# LiPo_Battery_Meter.net
KiCad netlist of a schematic drawn in EAGLE
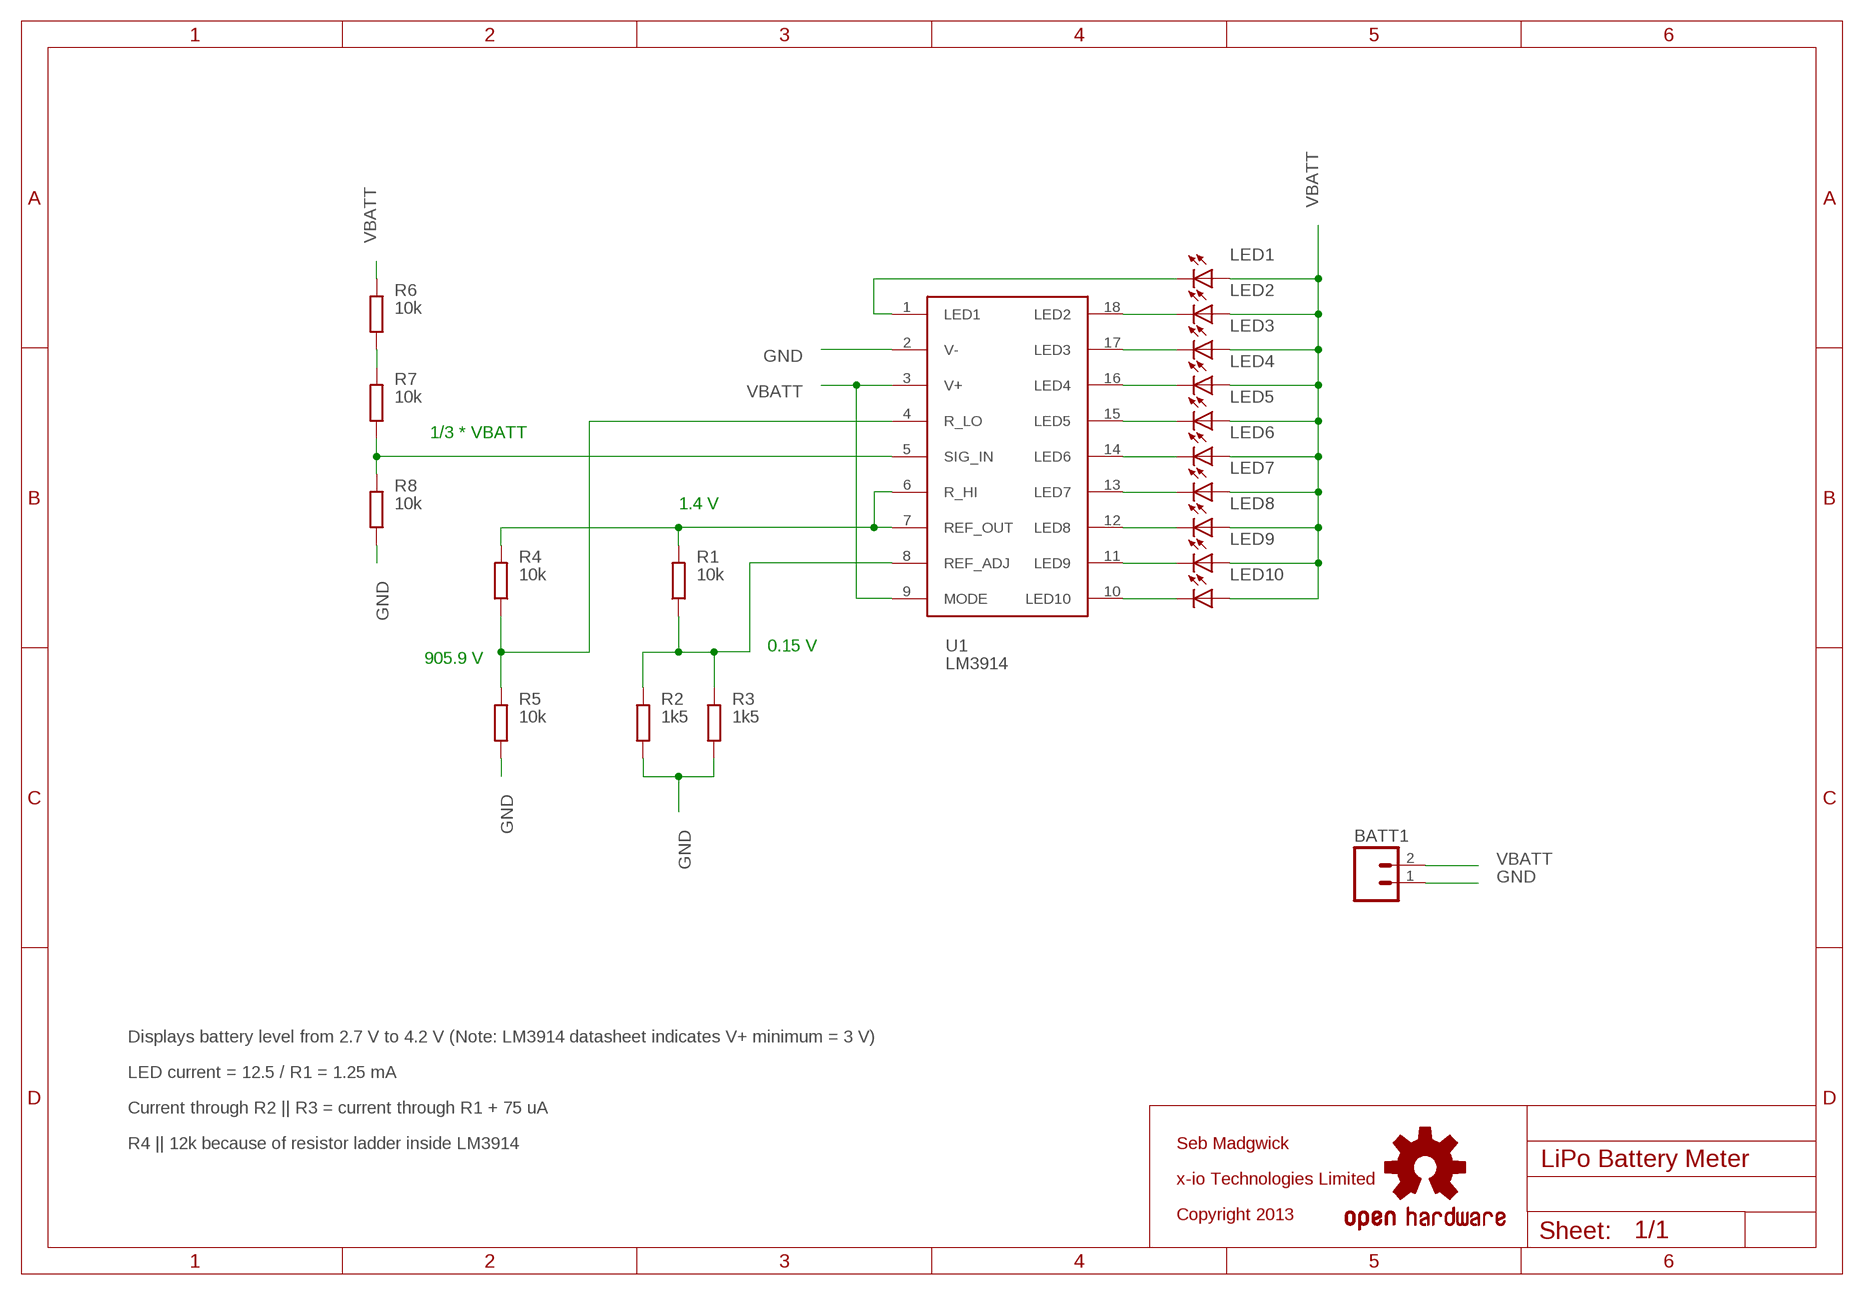
[diagram p0: schematic, sheet 1]

(export (version "E")
  (design (tool "Eeschema 10.0.6"))
  (components
    (comp (ref "BATT1")
      (value "M02-JST-2MM-SMT")
      (footprint "eagle-import:S2B-PH")
      (libsource (lib "eagle-import") (part "M02-JST-2MM-SMT"))
    )
    (comp (ref "LED1")
      (value "LEDCHIPLED_1206")
      (footprint "eagle-import:CHIPLED_1206")
      (libsource (lib "eagle-import") (part "LEDCHIPLED_1206"))
    )
    (comp (ref "LED2")
      (value "LEDCHIPLED_1206")
      (footprint "eagle-import:CHIPLED_1206")
      (libsource (lib "eagle-import") (part "LEDCHIPLED_1206"))
    )
    (comp (ref "LED3")
      (value "LEDCHIPLED_1206")
      (footprint "eagle-import:CHIPLED_1206")
      (libsource (lib "eagle-import") (part "LEDCHIPLED_1206"))
    )
    (comp (ref "LED4")
      (value "LEDCHIPLED_1206")
      (footprint "eagle-import:CHIPLED_1206")
      (libsource (lib "eagle-import") (part "LEDCHIPLED_1206"))
    )
    (comp (ref "LED5")
      (value "LEDCHIPLED_1206")
      (footprint "eagle-import:CHIPLED_1206")
      (libsource (lib "eagle-import") (part "LEDCHIPLED_1206"))
    )
    (comp (ref "LED6")
      (value "LEDCHIPLED_1206")
      (footprint "eagle-import:CHIPLED_1206")
      (libsource (lib "eagle-import") (part "LEDCHIPLED_1206"))
    )
    (comp (ref "LED7")
      (value "LEDCHIPLED_1206")
      (footprint "eagle-import:CHIPLED_1206")
      (libsource (lib "eagle-import") (part "LEDCHIPLED_1206"))
    )
    (comp (ref "LED8")
      (value "LEDCHIPLED_1206")
      (footprint "eagle-import:CHIPLED_1206")
      (libsource (lib "eagle-import") (part "LEDCHIPLED_1206"))
    )
    (comp (ref "LED9")
      (value "LEDCHIPLED_1206")
      (footprint "eagle-import:CHIPLED_1206")
      (libsource (lib "eagle-import") (part "LEDCHIPLED_1206"))
    )
    (comp (ref "LED10")
      (value "LEDCHIPLED_1206")
      (footprint "eagle-import:CHIPLED_1206")
      (libsource (lib "eagle-import") (part "LEDCHIPLED_1206"))
    )
    (comp (ref "R1")
      (value "10k")
      (footprint "eagle-import:M1206")
      (libsource (lib "eagle-import") (part "R-EU_M1206"))
    )
    (comp (ref "R2")
      (value "1k5")
      (footprint "eagle-import:M1206")
      (libsource (lib "eagle-import") (part "R-EU_M1206"))
    )
    (comp (ref "R3")
      (value "1k5")
      (footprint "eagle-import:M1206")
      (libsource (lib "eagle-import") (part "R-EU_M1206"))
    )
    (comp (ref "R4")
      (value "10k")
      (footprint "eagle-import:M1206")
      (libsource (lib "eagle-import") (part "R-EU_M1206"))
    )
    (comp (ref "R5")
      (value "10k")
      (footprint "eagle-import:M1206")
      (libsource (lib "eagle-import") (part "R-EU_M1206"))
    )
    (comp (ref "R6")
      (value "10k")
      (footprint "eagle-import:M1206")
      (libsource (lib "eagle-import") (part "R-EU_M1206"))
    )
    (comp (ref "R7")
      (value "10k")
      (footprint "eagle-import:M1206")
      (libsource (lib "eagle-import") (part "R-EU_M1206"))
    )
    (comp (ref "R8")
      (value "10k")
      (footprint "eagle-import:M1206")
      (libsource (lib "eagle-import") (part "R-EU_M1206"))
    )
    (comp (ref "U$2")
      (value "OSHW-LOGOM")
      (footprint "eagle-import:OSHW-LOGO-M")
      (libsource (lib "eagle-import") (part "OSHW-LOGOM"))
    )
    (comp (ref "U1")
      (value "LM3914")
      (footprint "eagle-import:DIL18")
      (libsource (lib "eagle-import") (part "LM3914"))
    )
  )
  (nets
    (net (code "1") (name "/GND") (class "Default")
      (node (ref "BATT1") (pin "1") (pinfunction "1_1") (pintype "passive"))
      (node (ref "R2") (pin "1") (pinfunction "1_1") (pintype "passive"))
      (node (ref "R3") (pin "1") (pinfunction "1_1") (pintype "passive"))
      (node (ref "R5") (pin "1") (pinfunction "1_1") (pintype "passive"))
      (node (ref "R8") (pin "1") (pinfunction "1_1") (pintype "passive"))
      (node (ref "U1") (pin "2") (pinfunction "V-_2") (pintype "bidirectional"))
    )
    (net (code "2") (name "/VBATT") (class "Default")
      (node (ref "BATT1") (pin "2") (pinfunction "2_2") (pintype "passive"))
      (node (ref "LED1") (pin "A") (pinfunction "A_A") (pintype "passive"))
      (node (ref "LED10") (pin "A") (pinfunction "A_A") (pintype "passive"))
      (node (ref "LED2") (pin "A") (pinfunction "A_A") (pintype "passive"))
      (node (ref "LED3") (pin "A") (pinfunction "A_A") (pintype "passive"))
      (node (ref "LED4") (pin "A") (pinfunction "A_A") (pintype "passive"))
      (node (ref "LED5") (pin "A") (pinfunction "A_A") (pintype "passive"))
      (node (ref "LED6") (pin "A") (pinfunction "A_A") (pintype "passive"))
      (node (ref "LED7") (pin "A") (pinfunction "A_A") (pintype "passive"))
      (node (ref "LED8") (pin "A") (pinfunction "A_A") (pintype "passive"))
      (node (ref "LED9") (pin "A") (pinfunction "A_A") (pintype "passive"))
      (node (ref "R6") (pin "2") (pinfunction "2_2") (pintype "passive"))
      (node (ref "U1") (pin "3") (pinfunction "V+_3") (pintype "bidirectional"))
      (node (ref "U1") (pin "9") (pinfunction "MODE_9") (pintype "bidirectional"))
    )
    (net (code "3") (name "Net-(R6-Pad1)") (class "Default")
      (node (ref "R6") (pin "1") (pinfunction "1_1") (pintype "passive"))
      (node (ref "R7") (pin "2") (pinfunction "2_2") (pintype "passive"))
    )
    (net (code "4") (name "Net-(U1-LED1)") (class "Default")
      (node (ref "LED1") (pin "C") (pinfunction "C_C") (pintype "passive"))
      (node (ref "U1") (pin "1") (pinfunction "LED1_1") (pintype "bidirectional"))
    )
    (net (code "5") (name "Net-(U1-LED2)") (class "Default")
      (node (ref "LED2") (pin "C") (pinfunction "C_C") (pintype "passive"))
      (node (ref "U1") (pin "18") (pinfunction "LED2_18") (pintype "bidirectional"))
    )
    (net (code "6") (name "Net-(U1-LED3)") (class "Default")
      (node (ref "LED3") (pin "C") (pinfunction "C_C") (pintype "passive"))
      (node (ref "U1") (pin "17") (pinfunction "LED3_17") (pintype "bidirectional"))
    )
    (net (code "7") (name "Net-(U1-LED4)") (class "Default")
      (node (ref "LED4") (pin "C") (pinfunction "C_C") (pintype "passive"))
      (node (ref "U1") (pin "16") (pinfunction "LED4_16") (pintype "bidirectional"))
    )
    (net (code "8") (name "Net-(U1-LED5)") (class "Default")
      (node (ref "LED5") (pin "C") (pinfunction "C_C") (pintype "passive"))
      (node (ref "U1") (pin "15") (pinfunction "LED5_15") (pintype "bidirectional"))
    )
    (net (code "9") (name "Net-(U1-LED6)") (class "Default")
      (node (ref "LED6") (pin "C") (pinfunction "C_C") (pintype "passive"))
      (node (ref "U1") (pin "14") (pinfunction "LED6_14") (pintype "bidirectional"))
    )
    (net (code "10") (name "Net-(U1-LED7)") (class "Default")
      (node (ref "LED7") (pin "C") (pinfunction "C_C") (pintype "passive"))
      (node (ref "U1") (pin "13") (pinfunction "LED7_13") (pintype "bidirectional"))
    )
    (net (code "11") (name "Net-(U1-LED8)") (class "Default")
      (node (ref "LED8") (pin "C") (pinfunction "C_C") (pintype "passive"))
      (node (ref "U1") (pin "12") (pinfunction "LED8_12") (pintype "bidirectional"))
    )
    (net (code "12") (name "Net-(U1-LED9)") (class "Default")
      (node (ref "LED9") (pin "C") (pinfunction "C_C") (pintype "passive"))
      (node (ref "U1") (pin "11") (pinfunction "LED9_11") (pintype "bidirectional"))
    )
    (net (code "13") (name "Net-(U1-LED10)") (class "Default")
      (node (ref "LED10") (pin "C") (pinfunction "C_C") (pintype "passive"))
      (node (ref "U1") (pin "10") (pinfunction "LED10_10") (pintype "bidirectional"))
    )
    (net (code "14") (name "Net-(U1-REF_ADJ)") (class "Default")
      (node (ref "R1") (pin "1") (pinfunction "1_1") (pintype "passive"))
      (node (ref "R2") (pin "2") (pinfunction "2_2") (pintype "passive"))
      (node (ref "R3") (pin "2") (pinfunction "2_2") (pintype "passive"))
      (node (ref "U1") (pin "8") (pinfunction "REF_ADJ_8") (pintype "bidirectional"))
    )
    (net (code "15") (name "Net-(U1-REF_OUT)") (class "Default")
      (node (ref "R1") (pin "2") (pinfunction "2_2") (pintype "passive"))
      (node (ref "R4") (pin "2") (pinfunction "2_2") (pintype "passive"))
      (node (ref "U1") (pin "6") (pinfunction "R_HI_6") (pintype "bidirectional"))
      (node (ref "U1") (pin "7") (pinfunction "REF_OUT_7") (pintype "bidirectional"))
    )
    (net (code "16") (name "Net-(U1-R_LO)") (class "Default")
      (node (ref "R4") (pin "1") (pinfunction "1_1") (pintype "passive"))
      (node (ref "R5") (pin "2") (pinfunction "2_2") (pintype "passive"))
      (node (ref "U1") (pin "4") (pinfunction "R_LO_4") (pintype "bidirectional"))
    )
    (net (code "17") (name "Net-(U1-SIG_IN)") (class "Default")
      (node (ref "R7") (pin "1") (pinfunction "1_1") (pintype "passive"))
      (node (ref "R8") (pin "2") (pinfunction "2_2") (pintype "passive"))
      (node (ref "U1") (pin "5") (pinfunction "SIG_IN_5") (pintype "bidirectional"))
    )
  )
)
